# lpc1768.net
KiCad netlist of a schematic drawn in EAGLE
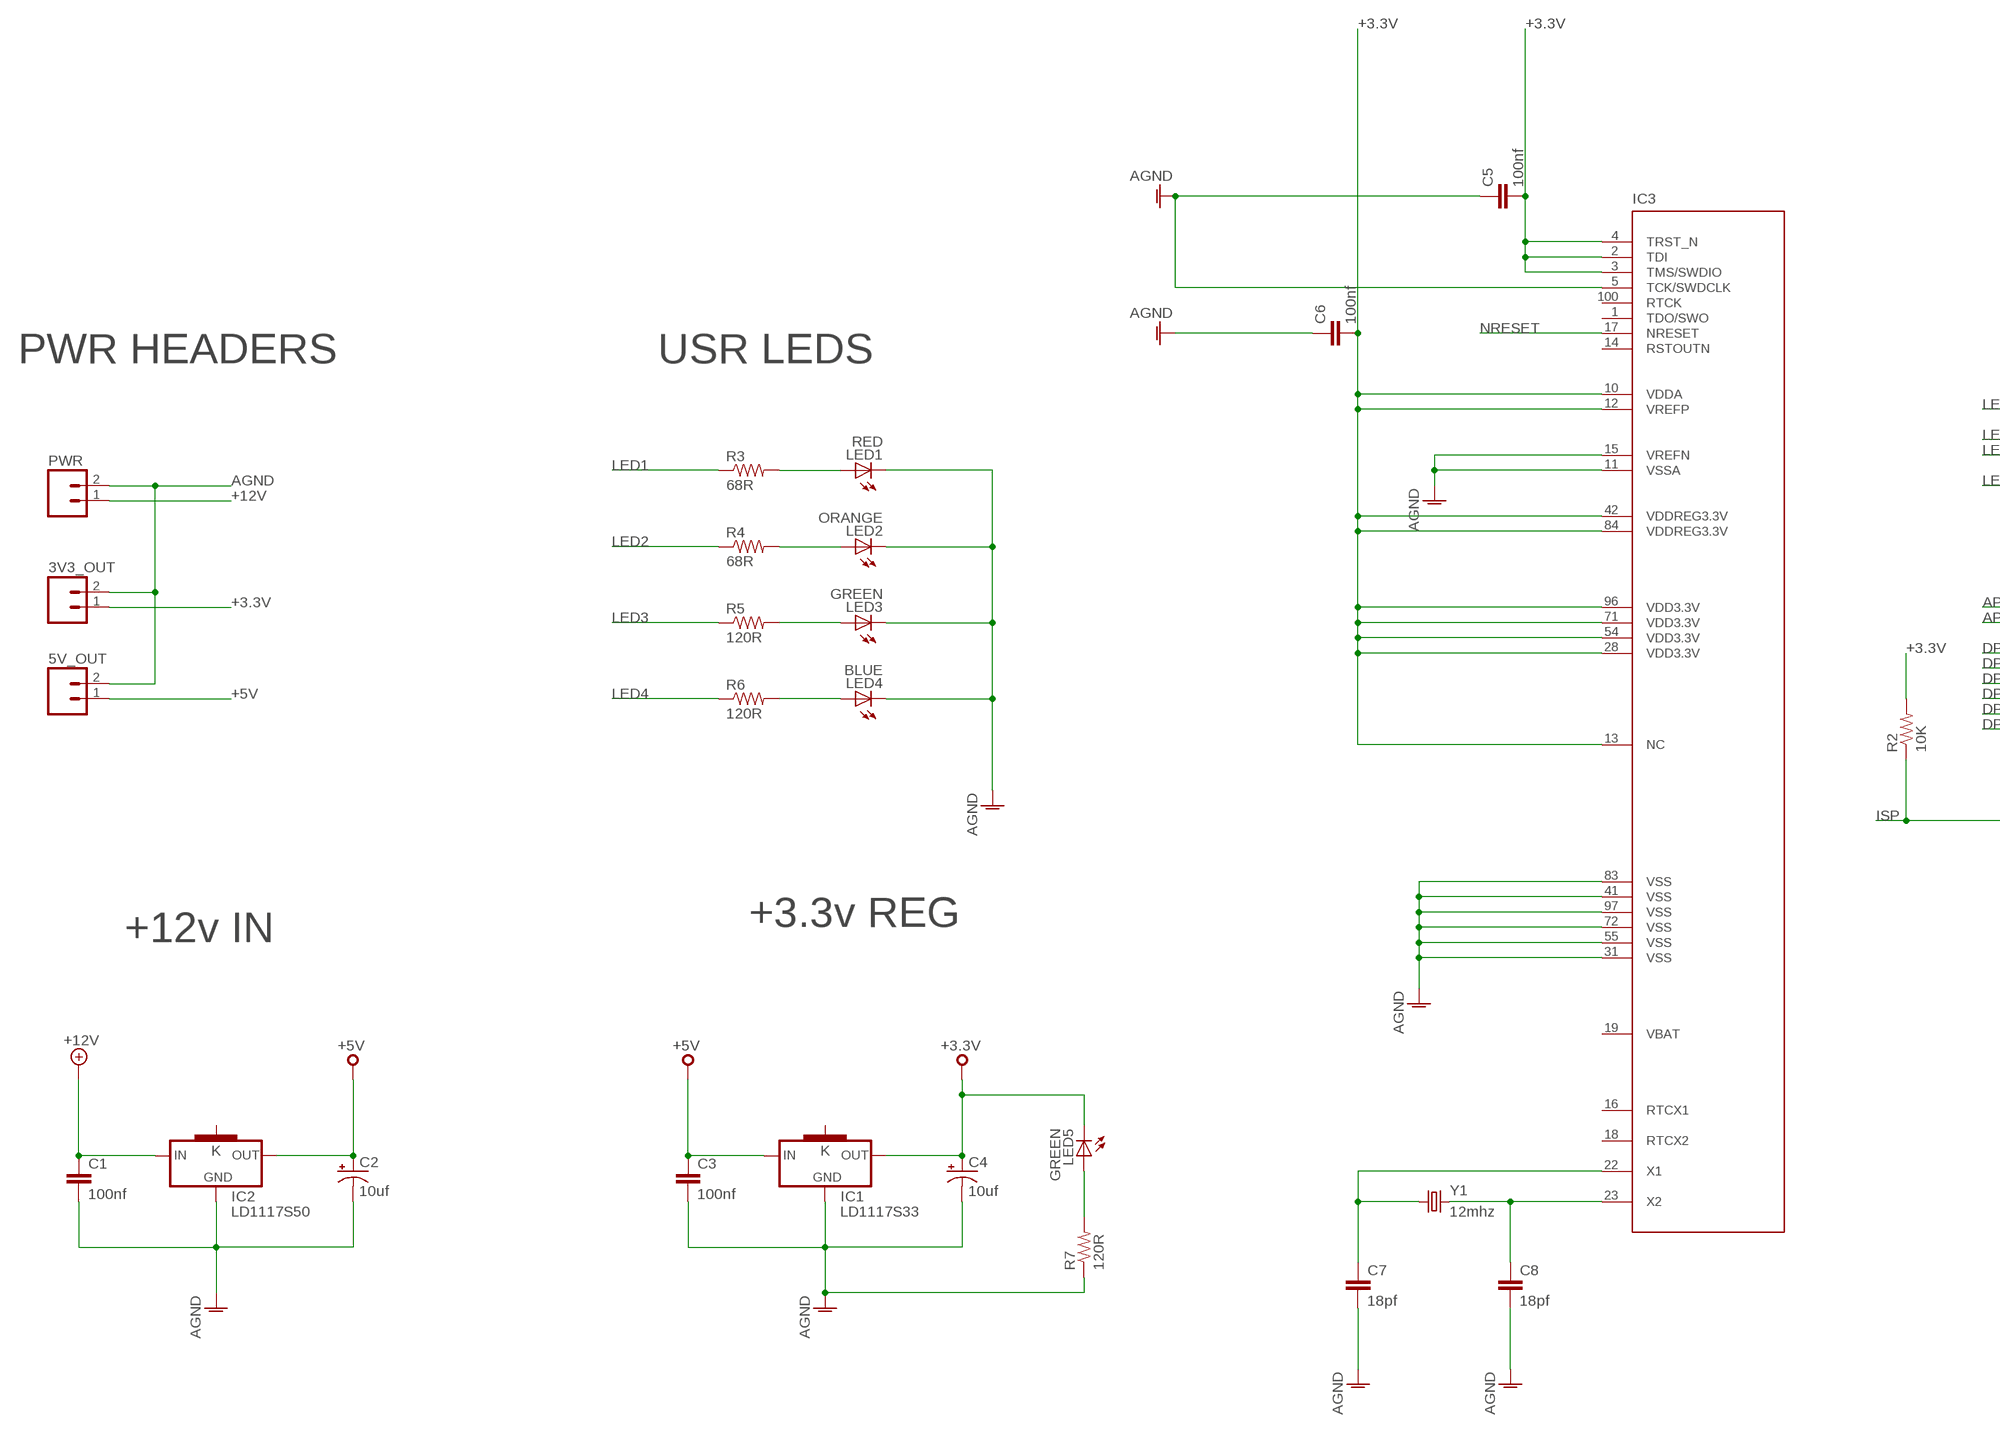
[diagram p0: schematic, sheet 1, part 1 of 2]
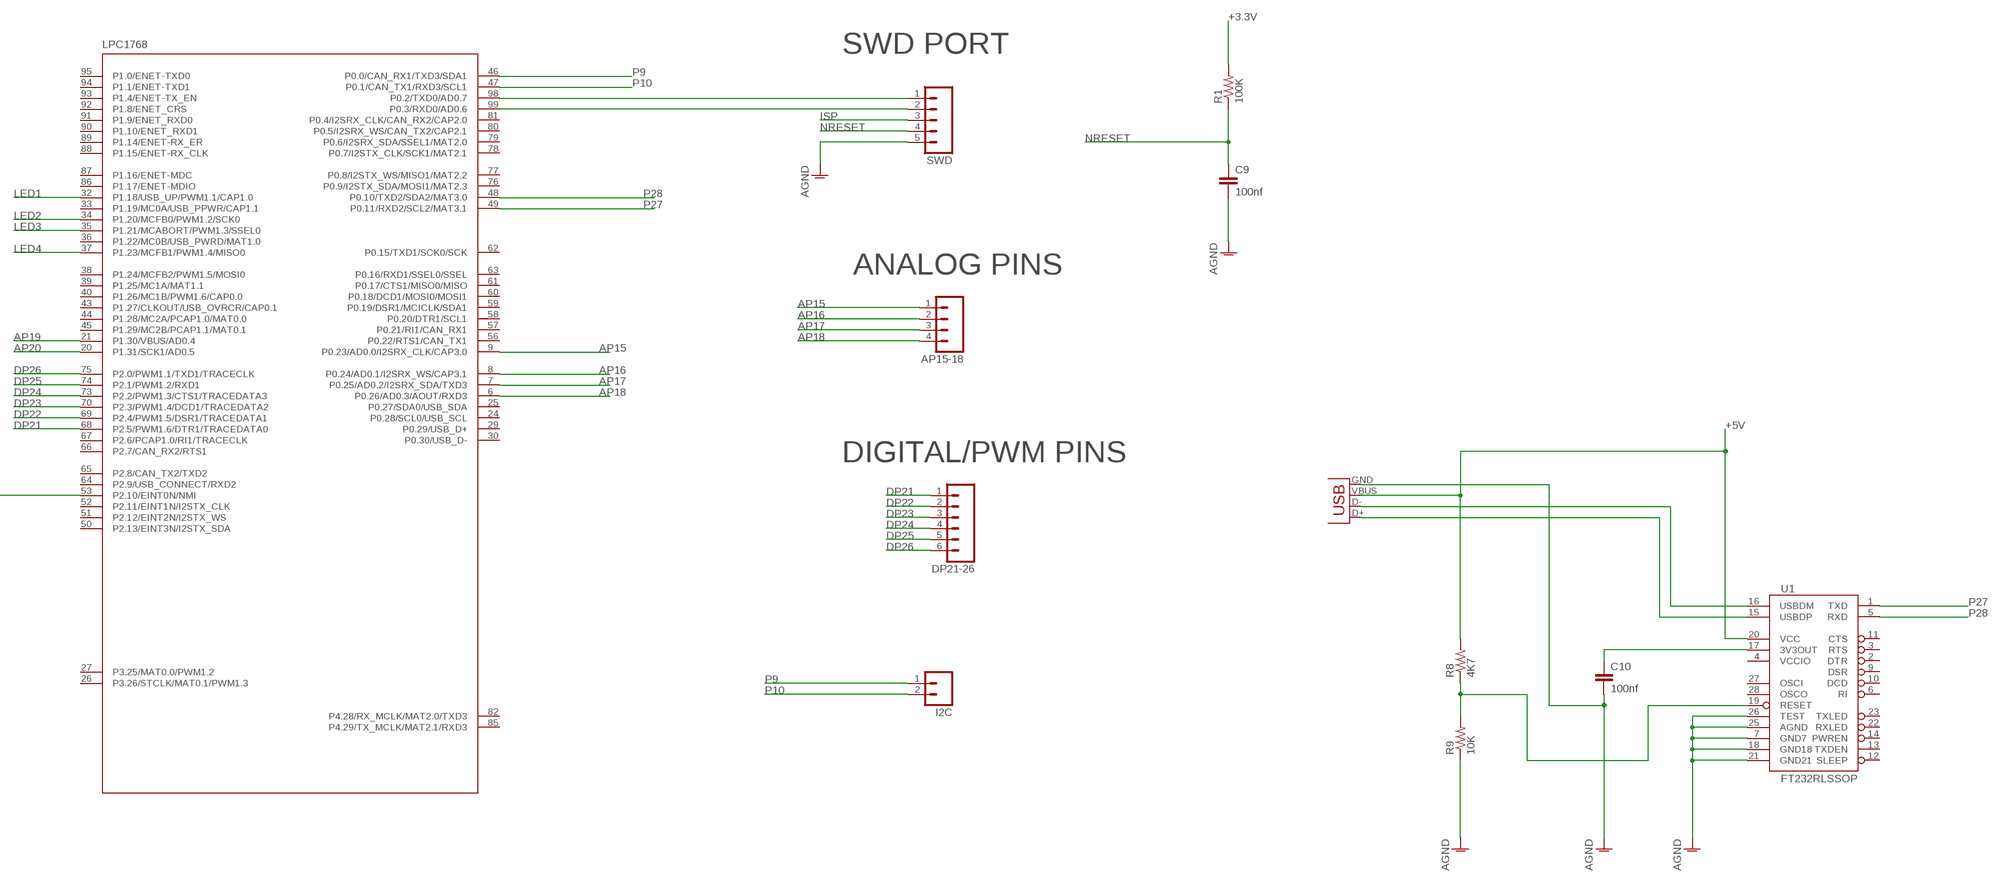
[diagram p1: schematic, sheet 1, part 2 of 2]

(export (version "E")
  (design (tool "Eeschema 10.0.6"))
  (components
    (comp (ref "3V3_OUT")
      (value "M02PTH3")
      (footprint "eagle-import:1X02_LONGPADS")
      (libsource (lib "eagle-import") (part "M02PTH3"))
    )
    (comp (ref "5V_OUT")
      (value "M02PTH3")
      (footprint "eagle-import:1X02_LONGPADS")
      (libsource (lib "eagle-import") (part "M02PTH3"))
    )
    (comp (ref "AP15-18")
      (value "M04LONGPADS")
      (footprint "eagle-import:1X04_LONGPADS")
      (libsource (lib "eagle-import") (part "M04LONGPADS"))
    )
    (comp (ref "C1")
      (value "100nf")
      (footprint "eagle-import:1206")
      (libsource (lib "eagle-import") (part "CAP1206"))
    )
    (comp (ref "C2")
      (value "10uf")
      (footprint "eagle-import:EIA3216-KIT")
      (libsource (lib "eagle-import") (part "CAP_POL1206-KIT"))
    )
    (comp (ref "C3")
      (value "100nf")
      (footprint "eagle-import:1206")
      (libsource (lib "eagle-import") (part "CAP1206"))
    )
    (comp (ref "C4")
      (value "10uf")
      (footprint "eagle-import:EIA3216-KIT")
      (libsource (lib "eagle-import") (part "CAP_POL1206-KIT"))
    )
    (comp (ref "C5")
      (value "100nf")
      (footprint "eagle-import:1206")
      (libsource (lib "eagle-import") (part "CAP1206"))
    )
    (comp (ref "C6")
      (value "100nf")
      (footprint "eagle-import:1206")
      (libsource (lib "eagle-import") (part "CAP1206"))
    )
    (comp (ref "C7")
      (value "18pf")
      (footprint "eagle-import:1206")
      (libsource (lib "eagle-import") (part "CAP1206"))
    )
    (comp (ref "C8")
      (value "18pf")
      (footprint "eagle-import:1206")
      (libsource (lib "eagle-import") (part "CAP1206"))
    )
    (comp (ref "C9")
      (value "100nf")
      (footprint "eagle-import:1206")
      (libsource (lib "eagle-import") (part "CAP1206"))
    )
    (comp (ref "C10")
      (value "100nf")
      (footprint "eagle-import:1206")
      (libsource (lib "eagle-import") (part "CAP1206"))
    )
    (comp (ref "DP21-26")
      (value "M06LONGPADS")
      (footprint "eagle-import:1X06_LONGPADS")
      (libsource (lib "eagle-import") (part "M06LONGPADS"))
    )
    (comp (ref "I2C")
      (value "M02PTH3")
      (footprint "eagle-import:1X02_LONGPADS")
      (libsource (lib "eagle-import") (part "M02PTH3"))
    )
    (comp (ref "IC1")
      (value "LD1117S33")
      (footprint "eagle-import:SOT223")
      (libsource (lib "eagle-import") (part "LD1117S33"))
    )
    (comp (ref "IC2")
      (value "LD1117S50")
      (footprint "eagle-import:SOT223")
      (libsource (lib "eagle-import") (part "LD1117S50"))
    )
    (comp (ref "IC3")
      (value "LPC1768")
      (footprint "eagle-import:LQFP100")
      (libsource (lib "eagle-import") (part "LPC1768"))
    )
    (comp (ref "LED1")
      (value "RED")
      (footprint "eagle-import:LED-1206")
      (libsource (lib "eagle-import") (part "LED1206"))
    )
    (comp (ref "LED2")
      (value "ORANGE")
      (footprint "eagle-import:LED-1206")
      (libsource (lib "eagle-import") (part "LED1206"))
    )
    (comp (ref "LED3")
      (value "GREEN")
      (footprint "eagle-import:LED-1206")
      (libsource (lib "eagle-import") (part "LED1206"))
    )
    (comp (ref "LED4")
      (value "BLUE")
      (footprint "eagle-import:LED-1206")
      (libsource (lib "eagle-import") (part "LED1206"))
    )
    (comp (ref "LED5")
      (value "GREEN")
      (footprint "eagle-import:LED-1206")
      (libsource (lib "eagle-import") (part "LED1206"))
    )
    (comp (ref "PWR")
      (value "M02PTH3")
      (footprint "eagle-import:1X02_LONGPADS")
      (libsource (lib "eagle-import") (part "M02PTH3"))
    )
    (comp (ref "R1")
      (value "100K")
      (footprint "eagle-import:1206")
      (libsource (lib "eagle-import") (part "RESISTOR1206"))
    )
    (comp (ref "R2")
      (value "10K")
      (footprint "eagle-import:1206")
      (libsource (lib "eagle-import") (part "RESISTOR1206"))
    )
    (comp (ref "R3")
      (value "68R")
      (footprint "eagle-import:1206")
      (libsource (lib "eagle-import") (part "RESISTOR1206"))
    )
    (comp (ref "R4")
      (value "68R")
      (footprint "eagle-import:1206")
      (libsource (lib "eagle-import") (part "RESISTOR1206"))
    )
    (comp (ref "R5")
      (value "120R")
      (footprint "eagle-import:1206")
      (libsource (lib "eagle-import") (part "RESISTOR1206"))
    )
    (comp (ref "R6")
      (value "120R")
      (footprint "eagle-import:1206")
      (libsource (lib "eagle-import") (part "RESISTOR1206"))
    )
    (comp (ref "R7")
      (value "120R")
      (footprint "eagle-import:1206")
      (libsource (lib "eagle-import") (part "RESISTOR1206"))
    )
    (comp (ref "R8")
      (value "4K7")
      (footprint "eagle-import:1206")
      (libsource (lib "eagle-import") (part "RESISTOR1206"))
    )
    (comp (ref "R9")
      (value "10K")
      (footprint "eagle-import:1206")
      (libsource (lib "eagle-import") (part "RESISTOR1206"))
    )
    (comp (ref "SWD")
      (value "M05PTH_LONGPADS")
      (footprint "eagle-import:1X05_LONGPADS")
      (libsource (lib "eagle-import") (part "M05PTH_LONGPADS"))
    )
    (comp (ref "U1")
      (value "FT232RLSSOP")
      (footprint "eagle-import:SSOP28DB")
      (libsource (lib "eagle-import") (part "FT232RLSSOP"))
    )
    (comp (ref "X1")
      (value "USB-MB-S")
      (footprint "eagle-import:USB-MB-S")
      (libsource (lib "eagle-import") (part "USB-MB-S"))
    )
    (comp (ref "Y1")
      (value "12mhz")
      (footprint "eagle-import:CRYSTAL-SMD-5X3")
      (libsource (lib "eagle-import") (part "CRYSTAL5X3"))
    )
  )
  (nets
    (net (code "1") (name "+3.3V") (class "Default")
      (node (ref "3V3_OUT") (pin "1") (pinfunction "1_1") (pintype "passive"))
      (node (ref "C4") (pin "A") (pinfunction "+_A") (pintype "passive"))
      (node (ref "C5") (pin "2") (pinfunction "2_2") (pintype "passive"))
      (node (ref "C6") (pin "2") (pinfunction "2_2") (pintype "passive"))
      (node (ref "IC1") (pin "2") (pinfunction "OUT_2") (pintype "passive"))
      (node (ref "IC3") (pin "10") (pinfunction "VDDA_10") (pintype "bidirectional"))
      (node (ref "IC3") (pin "12") (pinfunction "VREFP_12") (pintype "bidirectional"))
      (node (ref "IC3") (pin "13") (pinfunction "NC_13") (pintype "bidirectional"))
      (node (ref "IC3") (pin "2") (pinfunction "TDI_2") (pintype "bidirectional"))
      (node (ref "IC3") (pin "28") (pinfunction "VDD3.3V_28") (pintype "bidirectional"))
      (node (ref "IC3") (pin "3") (pinfunction "TMS/SWDIO_3") (pintype "bidirectional"))
      (node (ref "IC3") (pin "4") (pinfunction "TRST_N_4") (pintype "bidirectional"))
      (node (ref "IC3") (pin "42") (pinfunction "VDDREG3.3V_42") (pintype "bidirectional"))
      (node (ref "IC3") (pin "54") (pinfunction "VDD3.3V_54") (pintype "bidirectional"))
      (node (ref "IC3") (pin "71") (pinfunction "VDD3.3V_71") (pintype "bidirectional"))
      (node (ref "IC3") (pin "84") (pinfunction "VDDREG3.3V_84") (pintype "bidirectional"))
      (node (ref "IC3") (pin "96") (pinfunction "VDD3.3V_96") (pintype "bidirectional"))
      (node (ref "LED5") (pin "C") (pinfunction "C_C") (pintype "passive"))
      (node (ref "R1") (pin "2") (pinfunction "2_2") (pintype "passive"))
      (node (ref "R2") (pin "2") (pinfunction "2_2") (pintype "passive"))
    )
    (net (code "2") (name "+5V") (class "Default")
      (node (ref "5V_OUT") (pin "1") (pinfunction "1_1") (pintype "passive"))
      (node (ref "C2") (pin "A") (pinfunction "+_A") (pintype "passive"))
      (node (ref "C3") (pin "1") (pinfunction "1_1") (pintype "passive"))
      (node (ref "IC1") (pin "3") (pinfunction "IN_3") (pintype "input"))
      (node (ref "IC2") (pin "2") (pinfunction "OUT_2") (pintype "passive"))
      (node (ref "R8") (pin "2") (pinfunction "2_2") (pintype "passive"))
      (node (ref "U1") (pin "20") (pinfunction "VCC_20") (pintype "power_in"))
      (node (ref "X1") (pin "VBUS") (pinfunction "VBUS_VBUS") (pintype "bidirectional"))
    )
    (net (code "3") (name "+12V") (class "Default")
      (node (ref "C1") (pin "1") (pinfunction "1_1") (pintype "passive"))
      (node (ref "IC2") (pin "3") (pinfunction "IN_3") (pintype "input"))
      (node (ref "PWR") (pin "1") (pinfunction "1_1") (pintype "passive"))
    )
    (net (code "4") (name "/AP15") (class "Default")
      (node (ref "AP15-18") (pin "1") (pinfunction "1_1") (pintype "passive"))
      (node (ref "IC3") (pin "9") (pinfunction "P0.23/AD0.0/I2SRX_CLK/CAP3.0_9") (pintype "bidirectional"))
    )
    (net (code "5") (name "/AP16") (class "Default")
      (node (ref "AP15-18") (pin "2") (pinfunction "2_2") (pintype "passive"))
      (node (ref "IC3") (pin "8") (pinfunction "P0.24/AD0.1/I2SRX_WS/CAP3.1_8") (pintype "bidirectional"))
    )
    (net (code "6") (name "/AP17") (class "Default")
      (node (ref "AP15-18") (pin "3") (pinfunction "3_3") (pintype "passive"))
      (node (ref "IC3") (pin "7") (pinfunction "P0.25/AD0.2/I2SRX_SDA/TXD3_7") (pintype "bidirectional"))
    )
    (net (code "7") (name "/AP18") (class "Default")
      (node (ref "AP15-18") (pin "4") (pinfunction "4_4") (pintype "passive"))
      (node (ref "IC3") (pin "6") (pinfunction "P0.26/AD0.3/AOUT/RXD3_6") (pintype "bidirectional"))
    )
    (net (code "8") (name "/AP19") (class "Default")
      (node (ref "IC3") (pin "21") (pinfunction "P1.30/VBUS/AD0.4_21") (pintype "bidirectional"))
    )
    (net (code "9") (name "/AP20") (class "Default")
      (node (ref "IC3") (pin "20") (pinfunction "P1.31/SCK1/AD0.5_20") (pintype "bidirectional"))
    )
    (net (code "10") (name "/DP21") (class "Default")
      (node (ref "DP21-26") (pin "1") (pinfunction "1_1") (pintype "passive"))
      (node (ref "IC3") (pin "68") (pinfunction "P2.5/PWM1.6/DTR1/TRACEDATA0_68") (pintype "bidirectional"))
    )
    (net (code "11") (name "/DP22") (class "Default")
      (node (ref "DP21-26") (pin "2") (pinfunction "2_2") (pintype "passive"))
      (node (ref "IC3") (pin "69") (pinfunction "P2.4/PWM1.5/DSR1/TRACEDATA1_69") (pintype "bidirectional"))
    )
    (net (code "12") (name "/DP23") (class "Default")
      (node (ref "DP21-26") (pin "3") (pinfunction "3_3") (pintype "passive"))
      (node (ref "IC3") (pin "70") (pinfunction "P2.3/PWM1.4/DCD1/TRACEDATA2_70") (pintype "bidirectional"))
    )
    (net (code "13") (name "/DP24") (class "Default")
      (node (ref "DP21-26") (pin "4") (pinfunction "4_4") (pintype "passive"))
      (node (ref "IC3") (pin "73") (pinfunction "P2.2/PWM1.3/CTS1/TRACEDATA3_73") (pintype "bidirectional"))
    )
    (net (code "14") (name "/DP25") (class "Default")
      (node (ref "DP21-26") (pin "5") (pinfunction "5_5") (pintype "passive"))
      (node (ref "IC3") (pin "74") (pinfunction "P2.1/PWM1.2/RXD1_74") (pintype "bidirectional"))
    )
    (net (code "15") (name "/DP26") (class "Default")
      (node (ref "DP21-26") (pin "6") (pinfunction "6_6") (pintype "passive"))
      (node (ref "IC3") (pin "75") (pinfunction "P2.0/PWM1.1/TXD1/TRACECLK_75") (pintype "bidirectional"))
    )
    (net (code "16") (name "/ISP") (class "Default")
      (node (ref "IC3") (pin "53") (pinfunction "P2.10/EINT0N/NMI_53") (pintype "bidirectional"))
      (node (ref "R2") (pin "1") (pinfunction "1_1") (pintype "passive"))
      (node (ref "SWD") (pin "3") (pinfunction "3_3") (pintype "passive"))
    )
    (net (code "17") (name "/LED1") (class "Default")
      (node (ref "IC3") (pin "32") (pinfunction "P1.18/USB_UP/PWM1.1/CAP1.0_32") (pintype "bidirectional"))
      (node (ref "R3") (pin "1") (pinfunction "1_1") (pintype "passive"))
    )
    (net (code "18") (name "/LED2") (class "Default")
      (node (ref "IC3") (pin "34") (pinfunction "P1.20/MCFB0/PWM1.2/SCK0_34") (pintype "bidirectional"))
      (node (ref "R4") (pin "1") (pinfunction "1_1") (pintype "passive"))
    )
    (net (code "19") (name "/LED3") (class "Default")
      (node (ref "IC3") (pin "35") (pinfunction "P1.21/MCABORT/PWM1.3/SSEL0_35") (pintype "bidirectional"))
      (node (ref "R5") (pin "1") (pinfunction "1_1") (pintype "passive"))
    )
    (net (code "20") (name "/LED4") (class "Default")
      (node (ref "IC3") (pin "37") (pinfunction "P1.23/MCFB1/PWM1.4/MISO0_37") (pintype "bidirectional"))
      (node (ref "R6") (pin "1") (pinfunction "1_1") (pintype "passive"))
    )
    (net (code "21") (name "/NRESET") (class "Default")
      (node (ref "C9") (pin "1") (pinfunction "1_1") (pintype "passive"))
      (node (ref "IC3") (pin "17") (pinfunction "NRESET_17") (pintype "bidirectional"))
      (node (ref "R1") (pin "1") (pinfunction "1_1") (pintype "passive"))
      (node (ref "SWD") (pin "4") (pinfunction "4_4") (pintype "passive"))
    )
    (net (code "22") (name "/P9") (class "Default")
      (node (ref "I2C") (pin "1") (pinfunction "1_1") (pintype "passive"))
      (node (ref "IC3") (pin "46") (pinfunction "P0.0/CAN_RX1/TXD3/SDA1_46") (pintype "bidirectional"))
    )
    (net (code "23") (name "/P10") (class "Default")
      (node (ref "I2C") (pin "2") (pinfunction "2_2") (pintype "passive"))
      (node (ref "IC3") (pin "47") (pinfunction "P0.1/CAN_TX1/RXD3/SCL1_47") (pintype "bidirectional"))
    )
    (net (code "24") (name "/P27") (class "Default")
      (node (ref "IC3") (pin "49") (pinfunction "P0.11/RXD2/SCL2/MAT3.1_49") (pintype "bidirectional"))
      (node (ref "U1") (pin "1") (pinfunction "TXD_1") (pintype "output"))
    )
    (net (code "25") (name "/P28") (class "Default")
      (node (ref "IC3") (pin "48") (pinfunction "P0.10/TXD2/SDA2/MAT3.0_48") (pintype "bidirectional"))
      (node (ref "U1") (pin "5") (pinfunction "RXD_5") (pintype "input"))
    )
    (net (code "26") (name "/VCCIO") (class "Default")
      (node (ref "U1") (pin "4") (pinfunction "VCCIO_4") (pintype "power_in"))
    )
    (net (code "27") (name "AGND") (class "Default")
      (node (ref "3V3_OUT") (pin "2") (pinfunction "2_2") (pintype "passive"))
      (node (ref "5V_OUT") (pin "2") (pinfunction "2_2") (pintype "passive"))
      (node (ref "C1") (pin "2") (pinfunction "2_2") (pintype "passive"))
      (node (ref "C10") (pin "2") (pinfunction "2_2") (pintype "passive"))
      (node (ref "C2") (pin "C") (pinfunction "-_C") (pintype "passive"))
      (node (ref "C3") (pin "2") (pinfunction "2_2") (pintype "passive"))
      (node (ref "C4") (pin "C") (pinfunction "-_C") (pintype "passive"))
      (node (ref "C5") (pin "1") (pinfunction "1_1") (pintype "passive"))
      (node (ref "C6") (pin "1") (pinfunction "1_1") (pintype "passive"))
      (node (ref "C7") (pin "2") (pinfunction "2_2") (pintype "passive"))
      (node (ref "C8") (pin "2") (pinfunction "2_2") (pintype "passive"))
      (node (ref "C9") (pin "2") (pinfunction "2_2") (pintype "passive"))
      (node (ref "IC1") (pin "1") (pinfunction "GND_1") (pintype "input"))
      (node (ref "IC2") (pin "1") (pinfunction "GND_1") (pintype "input"))
      (node (ref "IC3") (pin "11") (pinfunction "VSSA_11") (pintype "bidirectional"))
      (node (ref "IC3") (pin "15") (pinfunction "VREFN_15") (pintype "bidirectional"))
      (node (ref "IC3") (pin "31") (pinfunction "VSS_31") (pintype "bidirectional"))
      (node (ref "IC3") (pin "41") (pinfunction "VSS_41") (pintype "bidirectional"))
      (node (ref "IC3") (pin "5") (pinfunction "TCK/SWDCLK_5") (pintype "bidirectional"))
      (node (ref "IC3") (pin "55") (pinfunction "VSS_55") (pintype "bidirectional"))
      (node (ref "IC3") (pin "72") (pinfunction "VSS_72") (pintype "bidirectional"))
      (node (ref "IC3") (pin "83") (pinfunction "VSS_83") (pintype "bidirectional"))
      (node (ref "IC3") (pin "97") (pinfunction "VSS_97") (pintype "bidirectional"))
      (node (ref "LED1") (pin "C") (pinfunction "C_C") (pintype "passive"))
      (node (ref "LED2") (pin "C") (pinfunction "C_C") (pintype "passive"))
      (node (ref "LED3") (pin "C") (pinfunction "C_C") (pintype "passive"))
      (node (ref "LED4") (pin "C") (pinfunction "C_C") (pintype "passive"))
      (node (ref "PWR") (pin "2") (pinfunction "2_2") (pintype "passive"))
      (node (ref "R7") (pin "1") (pinfunction "1_1") (pintype "passive"))
      (node (ref "R9") (pin "1") (pinfunction "1_1") (pintype "passive"))
      (node (ref "SWD") (pin "5") (pinfunction "5_5") (pintype "passive"))
      (node (ref "U1") (pin "18") (pinfunction "GND18_18") (pintype "power_in"))
      (node (ref "U1") (pin "21") (pinfunction "GND21_21") (pintype "power_in"))
      (node (ref "U1") (pin "25") (pinfunction "AGND_25") (pintype "power_in"))
      (node (ref "U1") (pin "26") (pinfunction "TEST_26") (pintype "input"))
      (node (ref "U1") (pin "7") (pinfunction "GND7_7") (pintype "power_in"))
      (node (ref "X1") (pin "GND") (pinfunction "GND_GND") (pintype "bidirectional"))
    )
    (net (code "28") (name "Net-(IC3-P0.2{slash}TXD0{slash}AD0.7)") (class "Default")
      (node (ref "IC3") (pin "98") (pinfunction "P0.2/TXD0/AD0.7_98") (pintype "bidirectional"))
      (node (ref "SWD") (pin "1") (pinfunction "1_1") (pintype "passive"))
    )
    (net (code "29") (name "Net-(IC3-P0.3{slash}RXD0{slash}AD0.6)") (class "Default")
      (node (ref "IC3") (pin "99") (pinfunction "P0.3/RXD0/AD0.6_99") (pintype "bidirectional"))
      (node (ref "SWD") (pin "2") (pinfunction "2_2") (pintype "passive"))
    )
    (net (code "30") (name "Net-(IC3-X1)") (class "Default")
      (node (ref "C7") (pin "1") (pinfunction "1_1") (pintype "passive"))
      (node (ref "IC3") (pin "22") (pinfunction "X1_22") (pintype "bidirectional"))
      (node (ref "Y1") (pin "1") (pinfunction "1_1") (pintype "passive"))
    )
    (net (code "31") (name "Net-(IC3-X2)") (class "Default")
      (node (ref "C8") (pin "1") (pinfunction "1_1") (pintype "passive"))
      (node (ref "IC3") (pin "23") (pinfunction "X2_23") (pintype "bidirectional"))
      (node (ref "Y1") (pin "3") (pinfunction "2_3") (pintype "passive"))
    )
    (net (code "32") (name "Net-(LED1-PadA)") (class "Default")
      (node (ref "LED1") (pin "A") (pinfunction "A_A") (pintype "passive"))
      (node (ref "R3") (pin "2") (pinfunction "2_2") (pintype "passive"))
    )
    (net (code "33") (name "Net-(LED2-PadA)") (class "Default")
      (node (ref "LED2") (pin "A") (pinfunction "A_A") (pintype "passive"))
      (node (ref "R4") (pin "2") (pinfunction "2_2") (pintype "passive"))
    )
    (net (code "34") (name "Net-(LED3-PadA)") (class "Default")
      (node (ref "LED3") (pin "A") (pinfunction "A_A") (pintype "passive"))
      (node (ref "R5") (pin "2") (pinfunction "2_2") (pintype "passive"))
    )
    (net (code "35") (name "Net-(LED4-PadA)") (class "Default")
      (node (ref "LED4") (pin "A") (pinfunction "A_A") (pintype "passive"))
      (node (ref "R6") (pin "2") (pinfunction "2_2") (pintype "passive"))
    )
    (net (code "36") (name "Net-(LED5-PadA)") (class "Default")
      (node (ref "LED5") (pin "A") (pinfunction "A_A") (pintype "passive"))
      (node (ref "R7") (pin "2") (pinfunction "2_2") (pintype "passive"))
    )
    (net (code "37") (name "Net-(U1-3V3OUT)") (class "Default")
      (node (ref "C10") (pin "1") (pinfunction "1_1") (pintype "passive"))
      (node (ref "U1") (pin "17") (pinfunction "3V3OUT_17") (pintype "output"))
    )
    (net (code "38") (name "Net-(U1-RESET)") (class "Default")
      (node (ref "R8") (pin "1") (pinfunction "1_1") (pintype "passive"))
      (node (ref "R9") (pin "2") (pinfunction "2_2") (pintype "passive"))
      (node (ref "U1") (pin "19") (pinfunction "RESET_19") (pintype "input"))
    )
    (net (code "39") (name "Net-(U1-USBDM)") (class "Default")
      (node (ref "U1") (pin "16") (pinfunction "USBDM_16") (pintype "bidirectional"))
      (node (ref "X1") (pin "D-") (pinfunction "D-_D-") (pintype "bidirectional"))
    )
    (net (code "40") (name "Net-(U1-USBDP)") (class "Default")
      (node (ref "U1") (pin "15") (pinfunction "USBDP_15") (pintype "bidirectional"))
      (node (ref "X1") (pin "D+") (pinfunction "D+_D+") (pintype "bidirectional"))
    )
    (net (code "41") (name "unconnected-(IC1-K-Pad4)") (class "Default")
      (node (ref "IC1") (pin "4") (pinfunction "K_4") (pintype "passive"))
    )
    (net (code "42") (name "unconnected-(IC2-K-Pad4)") (class "Default")
      (node (ref "IC2") (pin "4") (pinfunction "K_4") (pintype "passive"))
    )
    (net (code "43") (name "unconnected-(IC3-P0.4{slash}I2SRX_CLK{slash}CAN_RX2{slash}CAP2.0-Pad81)") (class "Default")
      (node (ref "IC3") (pin "81") (pinfunction "P0.4/I2SRX_CLK/CAN_RX2/CAP2.0_81") (pintype "bidirectional"))
    )
    (net (code "44") (name "unconnected-(IC3-P0.5{slash}I2SRX_WS{slash}CAN_TX2{slash}CAP2.1-Pad80)") (class "Default")
      (node (ref "IC3") (pin "80") (pinfunction "P0.5/I2SRX_WS/CAN_TX2/CAP2.1_80") (pintype "bidirectional"))
    )
    (net (code "45") (name "unconnected-(IC3-P0.6{slash}I2SRX_SDA{slash}SSEL1{slash}MAT2.0-Pad79)") (class "Default")
      (node (ref "IC3") (pin "79") (pinfunction "P0.6/I2SRX_SDA/SSEL1/MAT2.0_79") (pintype "bidirectional"))
    )
    (net (code "46") (name "unconnected-(IC3-P0.7{slash}I2STX_CLK{slash}SCK1{slash}MAT2.1-Pad78)") (class "Default")
      (node (ref "IC3") (pin "78") (pinfunction "P0.7/I2STX_CLK/SCK1/MAT2.1_78") (pintype "bidirectional"))
    )
    (net (code "47") (name "unconnected-(IC3-P0.8{slash}I2STX_WS{slash}MISO1{slash}MAT2.2-Pad77)") (class "Default")
      (node (ref "IC3") (pin "77") (pinfunction "P0.8/I2STX_WS/MISO1/MAT2.2_77") (pintype "bidirectional"))
    )
    (net (code "48") (name "unconnected-(IC3-P0.9{slash}I2STX_SDA{slash}MOSI1{slash}MAT2.3-Pad76)") (class "Default")
      (node (ref "IC3") (pin "76") (pinfunction "P0.9/I2STX_SDA/MOSI1/MAT2.3_76") (pintype "bidirectional"))
    )
    (net (code "49") (name "unconnected-(IC3-P0.15{slash}TXD1{slash}SCK0{slash}SCK-Pad62)") (class "Default")
      (node (ref "IC3") (pin "62") (pinfunction "P0.15/TXD1/SCK0/SCK_62") (pintype "bidirectional"))
    )
    (net (code "50") (name "unconnected-(IC3-P0.16{slash}RXD1{slash}SSEL0{slash}SSEL-Pad63)") (class "Default")
      (node (ref "IC3") (pin "63") (pinfunction "P0.16/RXD1/SSEL0/SSEL_63") (pintype "bidirectional"))
    )
    (net (code "51") (name "unconnected-(IC3-P0.17{slash}CTS1{slash}MISO0{slash}MISO-Pad61)") (class "Default")
      (node (ref "IC3") (pin "61") (pinfunction "P0.17/CTS1/MISO0/MISO_61") (pintype "bidirectional"))
    )
    (net (code "52") (name "unconnected-(IC3-P0.18{slash}DCD1{slash}MOSI0{slash}MOSI1-Pad60)") (class "Default")
      (node (ref "IC3") (pin "60") (pinfunction "P0.18/DCD1/MOSI0/MOSI1_60") (pintype "bidirectional"))
    )
    (net (code "53") (name "unconnected-(IC3-P0.19{slash}DSR1{slash}MCICLK{slash}SDA1-Pad59)") (class "Default")
      (node (ref "IC3") (pin "59") (pinfunction "P0.19/DSR1/MCICLK/SDA1_59") (pintype "bidirectional"))
    )
    (net (code "54") (name "unconnected-(IC3-P0.20{slash}DTR1{slash}SCL1-Pad58)") (class "Default")
      (node (ref "IC3") (pin "58") (pinfunction "P0.20/DTR1/SCL1_58") (pintype "bidirectional"))
    )
    (net (code "55") (name "unconnected-(IC3-P0.21{slash}RI1{slash}CAN_RX1-Pad57)") (class "Default")
      (node (ref "IC3") (pin "57") (pinfunction "P0.21/RI1/CAN_RX1_57") (pintype "bidirectional"))
    )
    (net (code "56") (name "unconnected-(IC3-P0.22{slash}RTS1{slash}CAN_TX1-Pad56)") (class "Default")
      (node (ref "IC3") (pin "56") (pinfunction "P0.22/RTS1/CAN_TX1_56") (pintype "bidirectional"))
    )
    (net (code "57") (name "unconnected-(IC3-P0.27{slash}SDA0{slash}USB_SDA-Pad25)") (class "Default")
      (node (ref "IC3") (pin "25") (pinfunction "P0.27/SDA0/USB_SDA_25") (pintype "bidirectional"))
    )
    (net (code "58") (name "unconnected-(IC3-P0.28{slash}SCL0{slash}USB_SCL-Pad24)") (class "Default")
      (node (ref "IC3") (pin "24") (pinfunction "P0.28/SCL0/USB_SCL_24") (pintype "bidirectional"))
    )
    (net (code "59") (name "unconnected-(IC3-P0.29{slash}USB_D+-Pad29)") (class "Default")
      (node (ref "IC3") (pin "29") (pinfunction "P0.29/USB_D+_29") (pintype "bidirectional"))
    )
    (net (code "60") (name "unconnected-(IC3-P0.30{slash}USB_D--Pad30)") (class "Default")
      (node (ref "IC3") (pin "30") (pinfunction "P0.30/USB_D-_30") (pintype "bidirectional"))
    )
    (net (code "61") (name "unconnected-(IC3-P1.0{slash}ENET-TXD0-Pad95)") (class "Default")
      (node (ref "IC3") (pin "95") (pinfunction "P1.0/ENET-TXD0_95") (pintype "bidirectional"))
    )
    (net (code "62") (name "unconnected-(IC3-P1.1{slash}ENET-TXD1-Pad94)") (class "Default")
      (node (ref "IC3") (pin "94") (pinfunction "P1.1/ENET-TXD1_94") (pintype "bidirectional"))
    )
    (net (code "63") (name "unconnected-(IC3-P1.4{slash}ENET-TX_EN-Pad93)") (class "Default")
      (node (ref "IC3") (pin "93") (pinfunction "P1.4/ENET-TX_EN_93") (pintype "bidirectional"))
    )
    (net (code "64") (name "unconnected-(IC3-P1.8{slash}ENET_CRS-Pad92)") (class "Default")
      (node (ref "IC3") (pin "92") (pinfunction "P1.8/ENET_CRS_92") (pintype "bidirectional"))
    )
    (net (code "65") (name "unconnected-(IC3-P1.9{slash}ENET_RXD0-Pad91)") (class "Default")
      (node (ref "IC3") (pin "91") (pinfunction "P1.9/ENET_RXD0_91") (pintype "bidirectional"))
    )
    (net (code "66") (name "unconnected-(IC3-P1.10{slash}ENET_RXD1-Pad90)") (class "Default")
      (node (ref "IC3") (pin "90") (pinfunction "P1.10/ENET_RXD1_90") (pintype "bidirectional"))
    )
    (net (code "67") (name "unconnected-(IC3-P1.14{slash}ENET-RX_ER-Pad89)") (class "Default")
      (node (ref "IC3") (pin "89") (pinfunction "P1.14/ENET-RX_ER_89") (pintype "bidirectional"))
    )
    (net (code "68") (name "unconnected-(IC3-P1.15{slash}ENET-RX_CLK-Pad88)") (class "Default")
      (node (ref "IC3") (pin "88") (pinfunction "P1.15/ENET-RX_CLK_88") (pintype "bidirectional"))
    )
    (net (code "69") (name "unconnected-(IC3-P1.16{slash}ENET-MDC-Pad87)") (class "Default")
      (node (ref "IC3") (pin "87") (pinfunction "P1.16/ENET-MDC_87") (pintype "bidirectional"))
    )
    (net (code "70") (name "unconnected-(IC3-P1.17{slash}ENET-MDIO-Pad86)") (class "Default")
      (node (ref "IC3") (pin "86") (pinfunction "P1.17/ENET-MDIO_86") (pintype "bidirectional"))
    )
    (net (code "71") (name "unconnected-(IC3-P1.19{slash}MC0A{slash}USB_PPWR{slash}CAP1.1-Pad33)") (class "Default")
      (node (ref "IC3") (pin "33") (pinfunction "P1.19/MC0A/USB_PPWR/CAP1.1_33") (pintype "bidirectional"))
    )
    (net (code "72") (name "unconnected-(IC3-P1.22{slash}MC0B{slash}USB_PWRD{slash}MAT1.0-Pad36)") (class "Default")
      (node (ref "IC3") (pin "36") (pinfunction "P1.22/MC0B/USB_PWRD/MAT1.0_36") (pintype "bidirectional"))
    )
    (net (code "73") (name "unconnected-(IC3-P1.24{slash}MCFB2{slash}PWM1.5{slash}MOSI0-Pad38)") (class "Default")
      (node (ref "IC3") (pin "38") (pinfunction "P1.24/MCFB2/PWM1.5/MOSI0_38") (pintype "bidirectional"))
    )
    (net (code "74") (name "unconnected-(IC3-P1.25{slash}MC1A{slash}MAT1.1-Pad39)") (class "Default")
      (node (ref "IC3") (pin "39") (pinfunction "P1.25/MC1A/MAT1.1_39") (pintype "bidirectional"))
    )
    (net (code "75") (name "unconnected-(IC3-P1.26{slash}MC1B{slash}PWM1.6{slash}CAP0.0-Pad40)") (class "Default")
      (node (ref "IC3") (pin "40") (pinfunction "P1.26/MC1B/PWM1.6/CAP0.0_40") (pintype "bidirectional"))
    )
    (net (code "76") (name "unconnected-(IC3-P1.27{slash}CLKOUT{slash}USB_OVRCR{slash}CAP0.1-Pad43)") (class "Default")
      (node (ref "IC3") (pin "43") (pinfunction "P1.27/CLKOUT/USB_OVRCR/CAP0.1_43") (pintype "bidirectional"))
    )
    (net (code "77") (name "unconnected-(IC3-P1.28{slash}MC2A{slash}PCAP1.0{slash}MAT0.0-Pad44)") (class "Default")
      (node (ref "IC3") (pin "44") (pinfunction "P1.28/MC2A/PCAP1.0/MAT0.0_44") (pintype "bidirectional"))
    )
    (net (code "78") (name "unconnected-(IC3-P1.29{slash}MC2B{slash}PCAP1.1{slash}MAT0.1-Pad45)") (class "Default")
      (node (ref "IC3") (pin "45") (pinfunction "P1.29/MC2B/PCAP1.1/MAT0.1_45") (pintype "bidirectional"))
    )
    (net (code "79") (name "unconnected-(IC3-P2.6{slash}PCAP1.0{slash}RI1{slash}TRACECLK-Pad67)") (class "Default")
      (node (ref "IC3") (pin "67") (pinfunction "P2.6/PCAP1.0/RI1/TRACECLK_67") (pintype "bidirectional"))
    )
    (net (code "80") (name "unconnected-(IC3-P2.7{slash}CAN_RX2{slash}RTS1-Pad66)") (class "Default")
      (node (ref "IC3") (pin "66") (pinfunction "P2.7/CAN_RX2/RTS1_66") (pintype "bidirectional"))
    )
    (net (code "81") (name "unconnected-(IC3-P2.8{slash}CAN_TX2{slash}TXD2-Pad65)") (class "Default")
      (node (ref "IC3") (pin "65") (pinfunction "P2.8/CAN_TX2/TXD2_65") (pintype "bidirectional"))
    )
    (net (code "82") (name "unconnected-(IC3-P2.9{slash}USB_CONNECT{slash}RXD2-Pad64)") (class "Default")
      (node (ref "IC3") (pin "64") (pinfunction "P2.9/USB_CONNECT/RXD2_64") (pintype "bidirectional"))
    )
    (net (code "83") (name "unconnected-(IC3-P2.11{slash}EINT1N{slash}I2STX_CLK-Pad52)") (class "Default")
      (node (ref "IC3") (pin "52") (pinfunction "P2.11/EINT1N/I2STX_CLK_52") (pintype "bidirectional"))
    )
    (net (code "84") (name "unconnected-(IC3-P2.12{slash}EINT2N{slash}I2STX_WS-Pad51)") (class "Default")
      (node (ref "IC3") (pin "51") (pinfunction "P2.12/EINT2N/I2STX_WS_51") (pintype "bidirectional"))
    )
    (net (code "85") (name "unconnected-(IC3-P2.13{slash}EINT3N{slash}I2STX_SDA-Pad50)") (class "Default")
      (node (ref "IC3") (pin "50") (pinfunction "P2.13/EINT3N/I2STX_SDA_50") (pintype "bidirectional"))
    )
    (net (code "86") (name "unconnected-(IC3-P3.25{slash}MAT0.0{slash}PWM1.2-Pad27)") (class "Default")
      (node (ref "IC3") (pin "27") (pinfunction "P3.25/MAT0.0/PWM1.2_27") (pintype "bidirectional"))
    )
    (net (code "87") (name "unconnected-(IC3-P3.26{slash}STCLK{slash}MAT0.1{slash}PWM1.3-Pad26)") (class "Default")
      (node (ref "IC3") (pin "26") (pinfunction "P3.26/STCLK/MAT0.1/PWM1.3_26") (pintype "bidirectional"))
    )
    (net (code "88") (name "unconnected-(IC3-P4.28{slash}RX_MCLK{slash}MAT2.0{slash}TXD3-Pad82)") (class "Default")
      (node (ref "IC3") (pin "82") (pinfunction "P4.28/RX_MCLK/MAT2.0/TXD3_82") (pintype "bidirectional"))
    )
    (net (code "89") (name "unconnected-(IC3-P4.29{slash}TX_MCLK{slash}MAT2.1{slash}RXD3-Pad85)") (class "Default")
      (node (ref "IC3") (pin "85") (pinfunction "P4.29/TX_MCLK/MAT2.1/RXD3_85") (pintype "bidirectional"))
    )
    (net (code "90") (name "unconnected-(IC3-RSTOUTN-Pad14)") (class "Default")
      (node (ref "IC3") (pin "14") (pinfunction "RSTOUTN_14") (pintype "bidirectional"))
    )
    (net (code "91") (name "unconnected-(IC3-RTCK-Pad100)") (class "Default")
      (node (ref "IC3") (pin "100") (pinfunction "RTCK_100") (pintype "bidirectional"))
    )
    (net (code "92") (name "unconnected-(IC3-RTCX1-Pad16)") (class "Default")
      (node (ref "IC3") (pin "16") (pinfunction "RTCX1_16") (pintype "bidirectional"))
    )
    (net (code "93") (name "unconnected-(IC3-RTCX2-Pad18)") (class "Default")
      (node (ref "IC3") (pin "18") (pinfunction "RTCX2_18") (pintype "bidirectional"))
    )
    (net (code "94") (name "unconnected-(IC3-TDO{slash}SWO-Pad1)") (class "Default")
      (node (ref "IC3") (pin "1") (pinfunction "TDO/SWO_1") (pintype "bidirectional"))
    )
    (net (code "95") (name "unconnected-(IC3-VBAT-Pad19)") (class "Default")
      (node (ref "IC3") (pin "19") (pinfunction "VBAT_19") (pintype "bidirectional"))
    )
    (net (code "96") (name "unconnected-(U1-CTS-Pad11)") (class "Default")
      (node (ref "U1") (pin "11") (pinfunction "CTS_11") (pintype "input"))
    )
    (net (code "97") (name "unconnected-(U1-DCD-Pad10)") (class "Default")
      (node (ref "U1") (pin "10") (pinfunction "DCD_10") (pintype "input"))
    )
    (net (code "98") (name "unconnected-(U1-DSR-Pad9)") (class "Default")
      (node (ref "U1") (pin "9") (pinfunction "DSR_9") (pintype "input"))
    )
    (net (code "99") (name "unconnected-(U1-DTR-Pad2)") (class "Default")
      (node (ref "U1") (pin "2") (pinfunction "DTR_2") (pintype "output"))
    )
    (net (code "100") (name "unconnected-(U1-OSCI-Pad27)") (class "Default")
      (node (ref "U1") (pin "27") (pinfunction "OSCI_27") (pintype "input"))
    )
    (net (code "101") (name "unconnected-(U1-OSCO-Pad28)") (class "Default")
      (node (ref "U1") (pin "28") (pinfunction "OSCO_28") (pintype "output"))
    )
    (net (code "102") (name "unconnected-(U1-PWREN-Pad14)") (class "Default")
      (node (ref "U1") (pin "14") (pinfunction "PWREN_14") (pintype "input"))
    )
    (net (code "103") (name "unconnected-(U1-RI-Pad6)") (class "Default")
      (node (ref "U1") (pin "6") (pinfunction "RI_6") (pintype "input"))
    )
    (net (code "104") (name "unconnected-(U1-RTS-Pad3)") (class "Default")
      (node (ref "U1") (pin "3") (pinfunction "RTS_3") (pintype "output"))
    )
    (net (code "105") (name "unconnected-(U1-RXLED-Pad22)") (class "Default")
      (node (ref "U1") (pin "22") (pinfunction "RXLED_22") (pintype "input"))
    )
    (net (code "106") (name "unconnected-(U1-SLEEP-Pad12)") (class "Default")
      (node (ref "U1") (pin "12") (pinfunction "SLEEP_12") (pintype "input"))
    )
    (net (code "107") (name "unconnected-(U1-TXDEN-Pad13)") (class "Default")
      (node (ref "U1") (pin "13") (pinfunction "TXDEN_13") (pintype "input"))
    )
    (net (code "108") (name "unconnected-(U1-TXLED-Pad23)") (class "Default")
      (node (ref "U1") (pin "23") (pinfunction "TXLED_23") (pintype "input"))
    )
  )
)
